# frontpanel.net
KiCad netlist of a schematic drawn in EAGLE
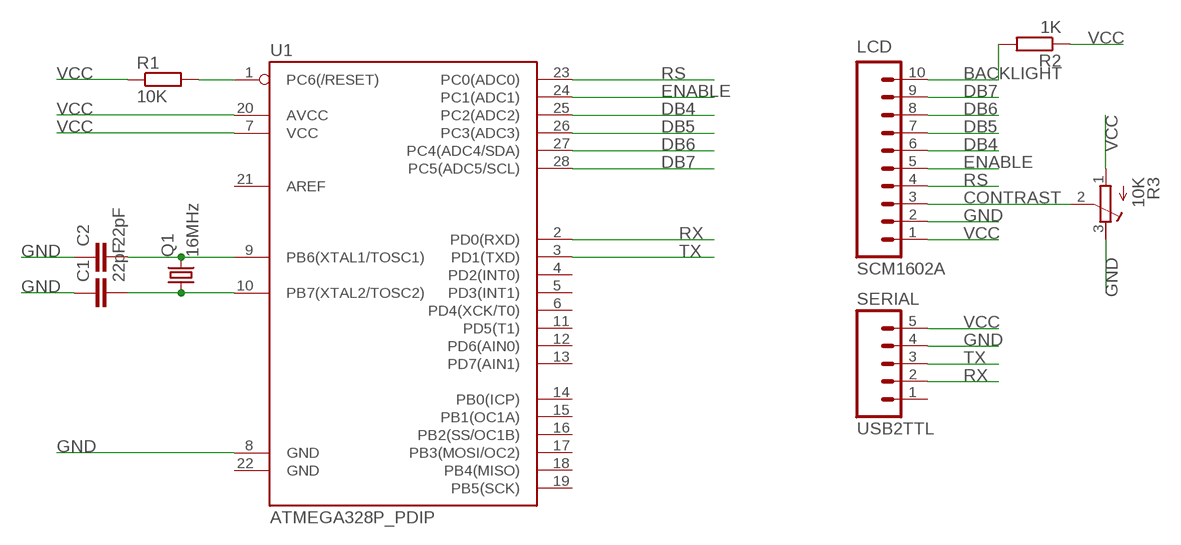
[diagram p0: schematic, sheet 1]

(export (version "E")
  (design (tool "Eeschema 10.0.6"))
  (components
    (comp (ref "C1")
      (value "22pF")
      (footprint "eagle-import:CAP-PTH-SMALL-KIT")
      (libsource (lib "eagle-import") (part "0.1UF-50V-20%(PTH)KIT-EZ"))
    )
    (comp (ref "C2")
      (value "22pF")
      (footprint "eagle-import:CAP-PTH-SMALL-KIT")
      (libsource (lib "eagle-import") (part "0.1UF-50V-20%(PTH)KIT-EZ"))
    )
    (comp (ref "LCD")
      (value "SCM1602A")
      (footprint "eagle-import:1X10")
      (libsource (lib "eagle-import") (part "M10SILK_FEMALE_PTH"))
    )
    (comp (ref "Q1")
      (value "16MHz")
      (footprint "eagle-import:HC49_S")
      (libsource (lib "eagle-import") (part "CRYSTALHC49S"))
    )
    (comp (ref "R1")
      (value "10K")
      (footprint "eagle-import:0204_7")
      (libsource (lib "eagle-import") (part "R-EU_0204/7"))
    )
    (comp (ref "R2")
      (value "1K")
      (footprint "eagle-import:0204_7")
      (libsource (lib "eagle-import") (part "R-EU_0204/7"))
    )
    (comp (ref "R3")
      (value "10K")
      (footprint "eagle-import:RTRIM64X")
      (libsource (lib "eagle-import") (part "R-TRIMM64X"))
    )
    (comp (ref "SERIAL")
      (value "USB2TTL")
      (footprint "eagle-import:1X05")
      (libsource (lib "eagle-import") (part "M05PTH"))
    )
    (comp (ref "U1")
      (value "ATMEGA328P_PDIP")
      (footprint "eagle-import:DIL28-3")
      (libsource (lib "eagle-import") (part "ATMEGA328P_PDIP"))
    )
  )
  (nets
    (net (code "1") (name "/BACKLIGHT") (class "Default")
      (node (ref "LCD") (pin "10") (pinfunction "10_10") (pintype "passive"))
      (node (ref "R2") (pin "2") (pinfunction "2_2") (pintype "passive"))
    )
    (net (code "2") (name "/CONTRAST") (class "Default")
      (node (ref "LCD") (pin "3") (pinfunction "3_3") (pintype "passive"))
      (node (ref "R3") (pin "2") (pinfunction "S_2") (pintype "passive"))
    )
    (net (code "3") (name "/DB4") (class "Default")
      (node (ref "LCD") (pin "6") (pinfunction "6_6") (pintype "passive"))
      (node (ref "U1") (pin "25") (pinfunction "PC2(ADC2)_25") (pintype "bidirectional"))
    )
    (net (code "4") (name "/DB5") (class "Default")
      (node (ref "LCD") (pin "7") (pinfunction "7_7") (pintype "passive"))
      (node (ref "U1") (pin "26") (pinfunction "PC3(ADC3)_26") (pintype "bidirectional"))
    )
    (net (code "5") (name "/DB6") (class "Default")
      (node (ref "LCD") (pin "8") (pinfunction "8_8") (pintype "passive"))
      (node (ref "U1") (pin "27") (pinfunction "PC4(ADC4/SDA)_27") (pintype "bidirectional"))
    )
    (net (code "6") (name "/DB7") (class "Default")
      (node (ref "LCD") (pin "9") (pinfunction "9_9") (pintype "passive"))
      (node (ref "U1") (pin "28") (pinfunction "PC5(ADC5/SCL)_28") (pintype "bidirectional"))
    )
    (net (code "7") (name "/ENABLE") (class "Default")
      (node (ref "LCD") (pin "5") (pinfunction "5_5") (pintype "passive"))
      (node (ref "U1") (pin "24") (pinfunction "PC1(ADC1)_24") (pintype "bidirectional"))
    )
    (net (code "8") (name "/GND") (class "Default")
      (node (ref "C1") (pin "1") (pinfunction "1_1") (pintype "passive"))
      (node (ref "C2") (pin "1") (pinfunction "1_1") (pintype "passive"))
      (node (ref "LCD") (pin "2") (pinfunction "2_2") (pintype "passive"))
      (node (ref "R3") (pin "3") (pinfunction "E_3") (pintype "passive"))
      (node (ref "SERIAL") (pin "4") (pinfunction "4_4") (pintype "passive"))
      (node (ref "U1") (pin "8") (pinfunction "GND_8") (pintype "bidirectional"))
    )
    (net (code "9") (name "/RS") (class "Default")
      (node (ref "LCD") (pin "4") (pinfunction "4_4") (pintype "passive"))
      (node (ref "U1") (pin "23") (pinfunction "PC0(ADC0)_23") (pintype "bidirectional"))
    )
    (net (code "10") (name "/RX") (class "Default")
      (node (ref "SERIAL") (pin "2") (pinfunction "2_2") (pintype "passive"))
      (node (ref "U1") (pin "2") (pinfunction "PD0(RXD)_2") (pintype "bidirectional"))
    )
    (net (code "11") (name "/TX") (class "Default")
      (node (ref "SERIAL") (pin "3") (pinfunction "3_3") (pintype "passive"))
      (node (ref "U1") (pin "3") (pinfunction "PD1(TXD)_3") (pintype "bidirectional"))
    )
    (net (code "12") (name "/VCC") (class "Default")
      (node (ref "LCD") (pin "1") (pinfunction "1_1") (pintype "passive"))
      (node (ref "R1") (pin "1") (pinfunction "1_1") (pintype "passive"))
      (node (ref "R2") (pin "1") (pinfunction "1_1") (pintype "passive"))
      (node (ref "R3") (pin "1") (pinfunction "A_1") (pintype "passive"))
      (node (ref "SERIAL") (pin "5") (pinfunction "5_5") (pintype "passive"))
      (node (ref "U1") (pin "20") (pinfunction "AVCC_20") (pintype "bidirectional"))
      (node (ref "U1") (pin "7") (pinfunction "VCC_7") (pintype "bidirectional"))
    )
    (net (code "13") (name "Net-(U1-PB6(XTAL1{slash}TOSC1))") (class "Default")
      (node (ref "C2") (pin "2") (pinfunction "2_2") (pintype "passive"))
      (node (ref "Q1") (pin "2") (pinfunction "2_2") (pintype "passive"))
      (node (ref "U1") (pin "9") (pinfunction "PB6(XTAL1/TOSC1)_9") (pintype "bidirectional"))
    )
    (net (code "14") (name "Net-(U1-PB7(XTAL2{slash}TOSC2))") (class "Default")
      (node (ref "C1") (pin "2") (pinfunction "2_2") (pintype "passive"))
      (node (ref "Q1") (pin "1") (pinfunction "1_1") (pintype "passive"))
      (node (ref "U1") (pin "10") (pinfunction "PB7(XTAL2/TOSC2)_10") (pintype "bidirectional"))
    )
    (net (code "15") (name "Net-(U1-PC6({slash}RESET))") (class "Default")
      (node (ref "R1") (pin "2") (pinfunction "2_2") (pintype "passive"))
      (node (ref "U1") (pin "1") (pinfunction "PC6(/RESET)_1") (pintype "bidirectional"))
    )
    (net (code "16") (name "unconnected-(SERIAL-Pad1)") (class "Default")
      (node (ref "SERIAL") (pin "1") (pinfunction "1_1") (pintype "passive"))
    )
    (net (code "17") (name "unconnected-(U1-AREF-Pad21)") (class "Default")
      (node (ref "U1") (pin "21") (pinfunction "AREF_21") (pintype "bidirectional"))
    )
    (net (code "18") (name "unconnected-(U1-GND-Pad22)") (class "Default")
      (node (ref "U1") (pin "22") (pinfunction "GND_22") (pintype "bidirectional"))
    )
    (net (code "19") (name "unconnected-(U1-PB0(ICP)-Pad14)") (class "Default")
      (node (ref "U1") (pin "14") (pinfunction "PB0(ICP)_14") (pintype "bidirectional"))
    )
    (net (code "20") (name "unconnected-(U1-PB1(OC1A)-Pad15)") (class "Default")
      (node (ref "U1") (pin "15") (pinfunction "PB1(OC1A)_15") (pintype "bidirectional"))
    )
    (net (code "21") (name "unconnected-(U1-PB2(SS{slash}OC1B)-Pad16)") (class "Default")
      (node (ref "U1") (pin "16") (pinfunction "PB2(SS/OC1B)_16") (pintype "bidirectional"))
    )
    (net (code "22") (name "unconnected-(U1-PB3(MOSI{slash}OC2)-Pad17)") (class "Default")
      (node (ref "U1") (pin "17") (pinfunction "PB3(MOSI/OC2)_17") (pintype "bidirectional"))
    )
    (net (code "23") (name "unconnected-(U1-PB4(MISO)-Pad18)") (class "Default")
      (node (ref "U1") (pin "18") (pinfunction "PB4(MISO)_18") (pintype "bidirectional"))
    )
    (net (code "24") (name "unconnected-(U1-PB5(SCK)-Pad19)") (class "Default")
      (node (ref "U1") (pin "19") (pinfunction "PB5(SCK)_19") (pintype "bidirectional"))
    )
    (net (code "25") (name "unconnected-(U1-PD2(INT0)-Pad4)") (class "Default")
      (node (ref "U1") (pin "4") (pinfunction "PD2(INT0)_4") (pintype "bidirectional"))
    )
    (net (code "26") (name "unconnected-(U1-PD3(INT1)-Pad5)") (class "Default")
      (node (ref "U1") (pin "5") (pinfunction "PD3(INT1)_5") (pintype "bidirectional"))
    )
    (net (code "27") (name "unconnected-(U1-PD4(XCK{slash}T0)-Pad6)") (class "Default")
      (node (ref "U1") (pin "6") (pinfunction "PD4(XCK/T0)_6") (pintype "bidirectional"))
    )
    (net (code "28") (name "unconnected-(U1-PD5(T1)-Pad11)") (class "Default")
      (node (ref "U1") (pin "11") (pinfunction "PD5(T1)_11") (pintype "bidirectional"))
    )
    (net (code "29") (name "unconnected-(U1-PD6(AIN0)-Pad12)") (class "Default")
      (node (ref "U1") (pin "12") (pinfunction "PD6(AIN0)_12") (pintype "bidirectional"))
    )
    (net (code "30") (name "unconnected-(U1-PD7(AIN1)-Pad13)") (class "Default")
      (node (ref "U1") (pin "13") (pinfunction "PD7(AIN1)_13") (pintype "bidirectional"))
    )
  )
)
